# Connector_Sheet.net
KiCad netlist of a schematic drawn in Altium Designer
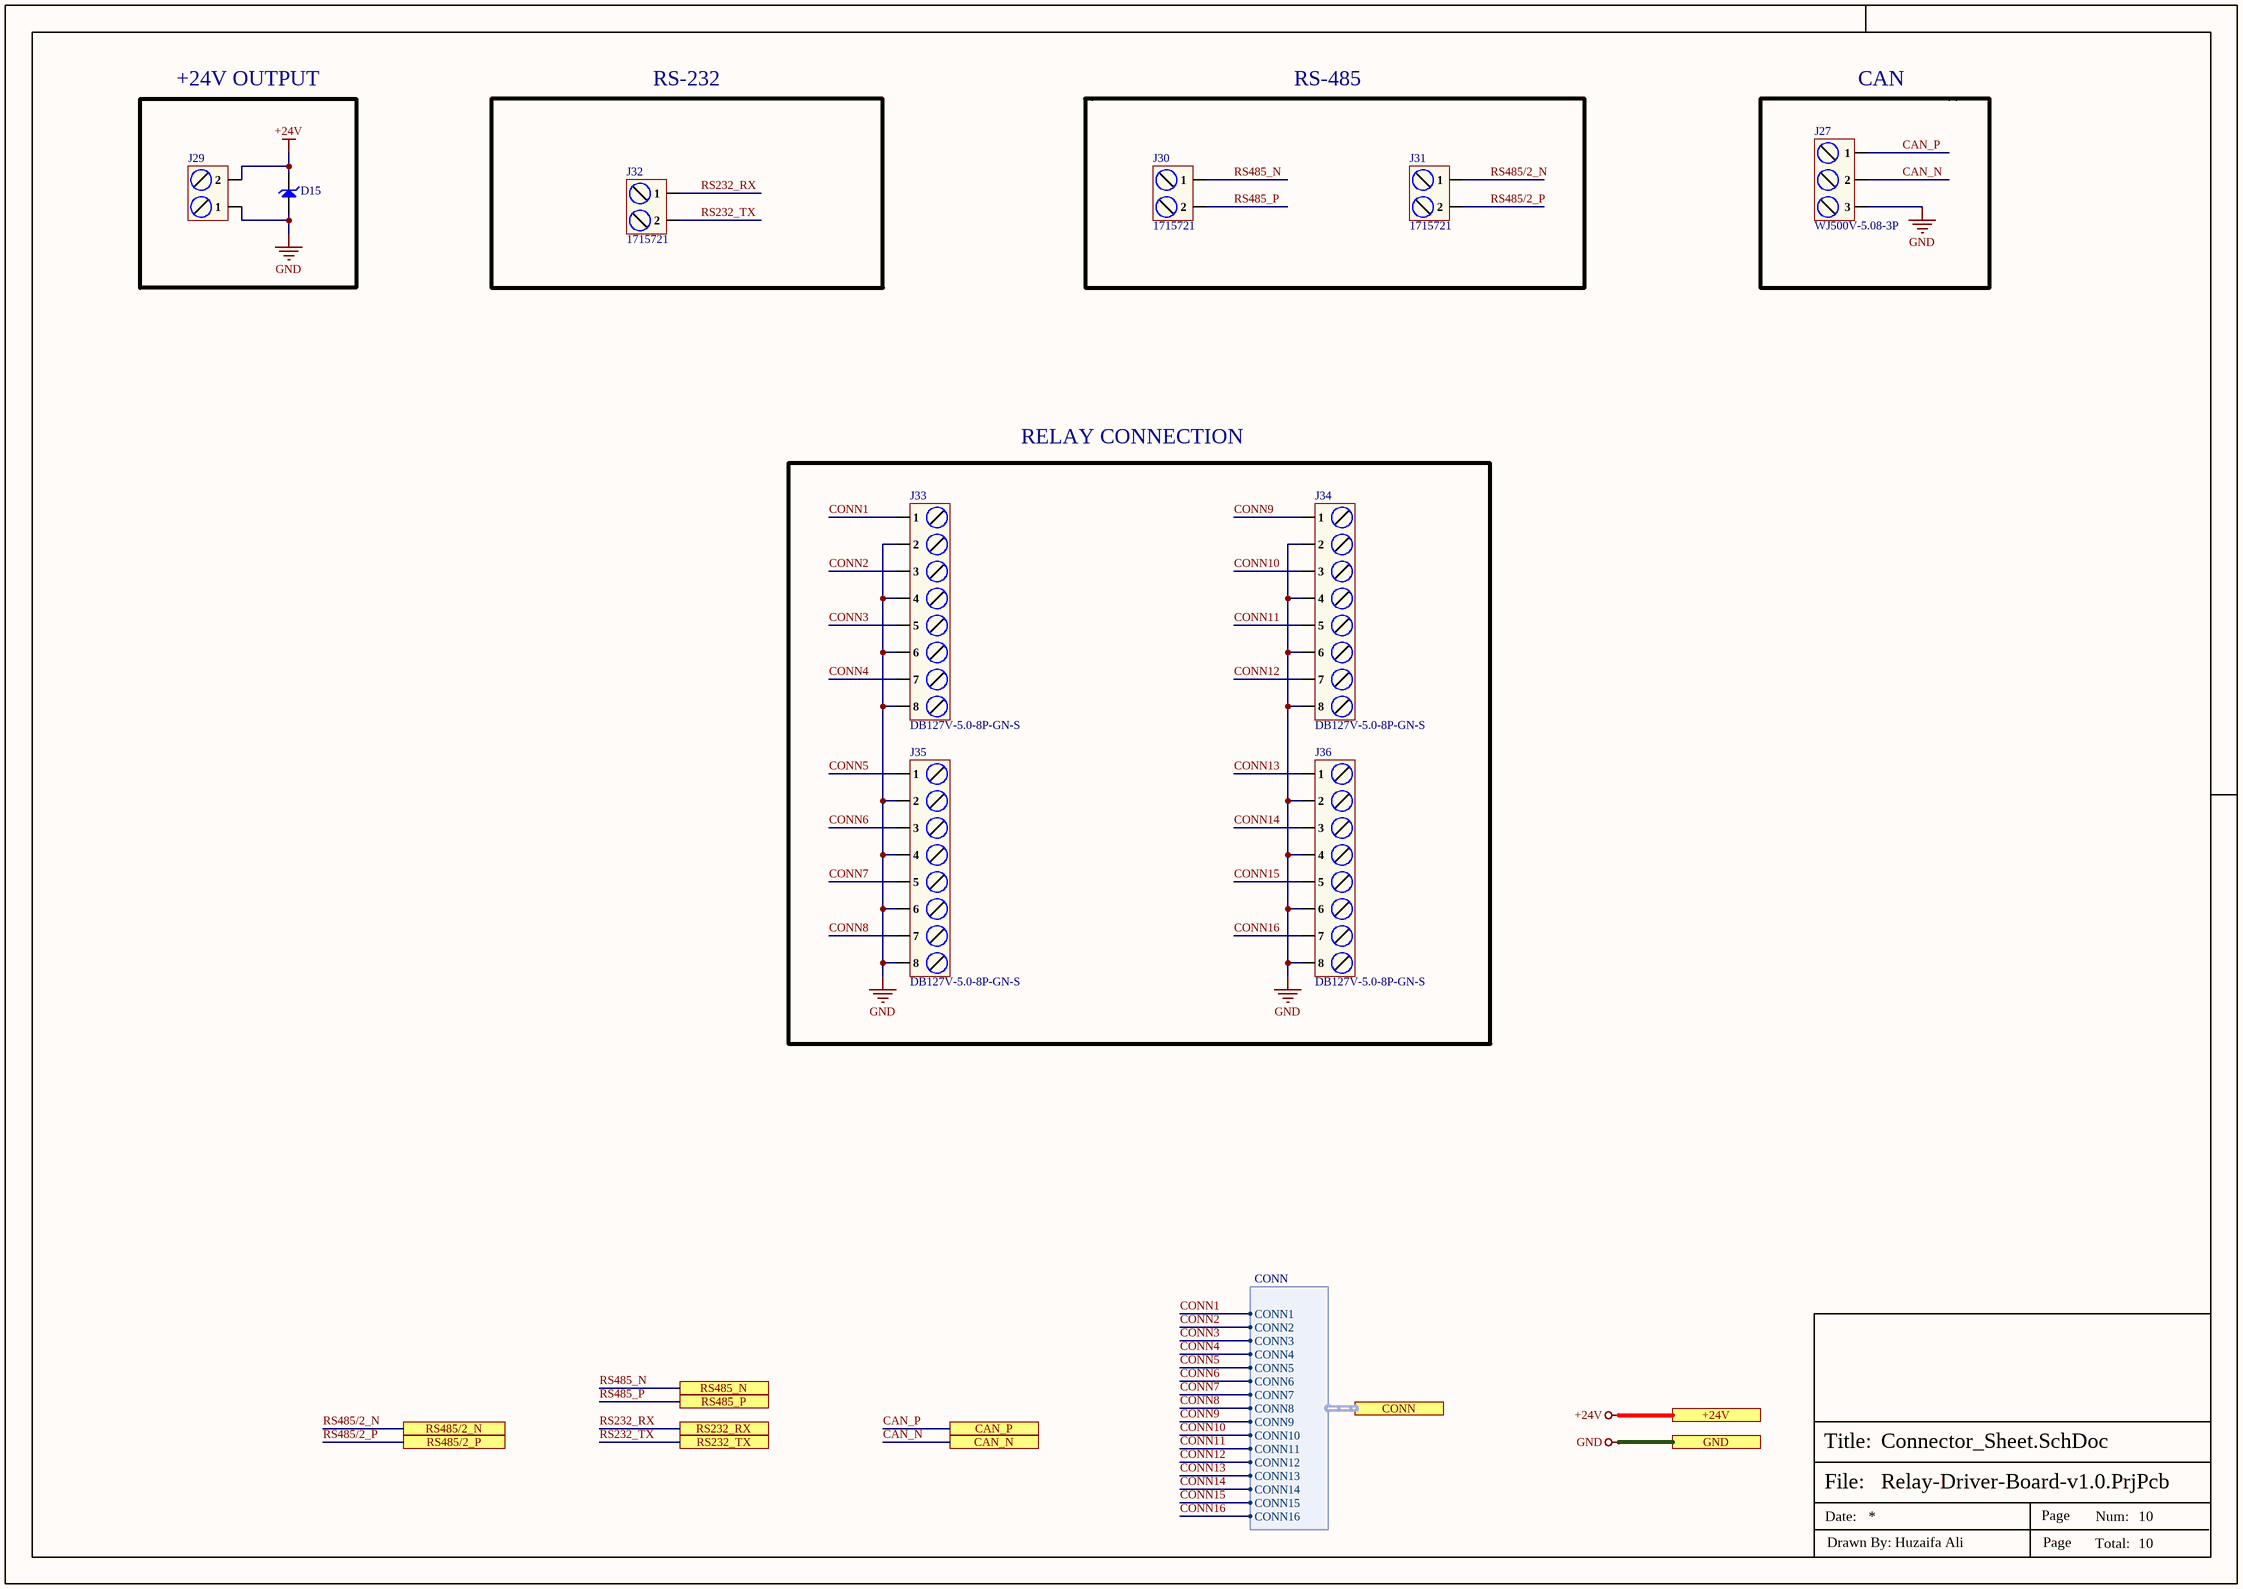
[diagram p0: Connector_Sheet.SchDoc]

(export (version "E")
  (design (tool "Eeschema 10.0.6"))
  (components
    (comp (ref "D15")
      (value "SMBJ28A-13-F")
      (footprint "SMB_")
      (description "TVS DIODE 28VWM 45.4VC SMB")
      (fields (field (name "MANUFACTURER") "Diodes"))
      (libsource (lib "eSpark Libraries") (part "SMBJ28A-13-F"))
    )
    (comp (ref "J27")
      (value "WJ500V-5.08-3P")
      (footprint "WJ500V-5.08-3P")
      (fields (field (name "MANUFACTURER") "Ningbo Kangnex Elec") (field (name "LCSC PART NUMBER") "C72334"))
      (libsource (lib "eSpark Libraries") (part "WJ500V-5.08-3P"))
    )
    (comp (ref "J29")
      (value "MXHB9500-9.5-02P-BK01-Cu-S-A")
      (footprint "MXHB9500-9.5-02P-BK01-Cu-S-A")
      (fields (field (name "MANUFACTURER") "MAX") (field (name "LCSC PART NUMBER") "C7542168"))
      (libsource (lib "eSpark Libraries") (part "MXHB9500-9.5-02P-BK01-Cu-S-A"))
    )
    (comp (ref "J30")
      (value "1715721")
      (footprint "1715721")
      (description "TERM BLK 2P SIDE ENT 5.08MM PCB")
      (fields (field (name "MANUFACTURER") "Phoenix Contact"))
      (libsource (lib "eSpark Libraries") (part "1715721"))
    )
    (comp (ref "J31")
      (value "1715721")
      (footprint "1715721")
      (description "TERM BLK 2P SIDE ENT 5.08MM PCB")
      (fields (field (name "MANUFACTURER") "Phoenix Contact"))
      (libsource (lib "eSpark Libraries") (part "1715721"))
    )
    (comp (ref "J32")
      (value "1715721")
      (footprint "1715721")
      (description "TERM BLK 2P SIDE ENT 5.08MM PCB")
      (fields (field (name "MANUFACTURER") "Phoenix Contact"))
      (libsource (lib "eSpark Libraries") (part "1715721"))
    )
    (comp (ref "J33")
      (value "DB127V-5.0-8P-GN-S")
      (footprint "DB127V-5.0-8P-GN-S")
      (description "1x8P -40℃~+105℃ 15A 250V Green 14~26 Straight 5mm 1.5 1 8 Plugin,P=5mm Screw Terminal Blocks ROHS")
      (fields (field (name "LCSC PART NUMBER") "C430626") (field (name "MANUFACTURER") "DIBO"))
      (libsource (lib "eSpark Libraries") (part "DB127V-5.0-8P-GN-S"))
    )
    (comp (ref "J34")
      (value "DB127V-5.0-8P-GN-S")
      (footprint "DB127V-5.0-8P-GN-S")
      (description "1x8P -40℃~+105℃ 15A 250V Green 14~26 Straight 5mm 1.5 1 8 Plugin,P=5mm Screw Terminal Blocks ROHS")
      (fields (field (name "LCSC PART NUMBER") "C430626") (field (name "MANUFACTURER") "DIBO"))
      (libsource (lib "eSpark Libraries") (part "DB127V-5.0-8P-GN-S"))
    )
    (comp (ref "J35")
      (value "DB127V-5.0-8P-GN-S")
      (footprint "DB127V-5.0-8P-GN-S")
      (description "1x8P -40℃~+105℃ 15A 250V Green 14~26 Straight 5mm 1.5 1 8 Plugin,P=5mm Screw Terminal Blocks ROHS")
      (fields (field (name "LCSC PART NUMBER") "C430626") (field (name "MANUFACTURER") "DIBO"))
      (libsource (lib "eSpark Libraries") (part "DB127V-5.0-8P-GN-S"))
    )
    (comp (ref "J36")
      (value "DB127V-5.0-8P-GN-S")
      (footprint "DB127V-5.0-8P-GN-S")
      (description "1x8P -40℃~+105℃ 15A 250V Green 14~26 Straight 5mm 1.5 1 8 Plugin,P=5mm Screw Terminal Blocks ROHS")
      (fields (field (name "LCSC PART NUMBER") "C430626") (field (name "MANUFACTURER") "DIBO"))
      (libsource (lib "eSpark Libraries") (part "DB127V-5.0-8P-GN-S"))
    )
  )
  (nets
    (net (code "2") (name "+24V") (class "Default")
      (node (ref "D15") (pin "2") (pinfunction "K_2") (pintype "passive"))
      (node (ref "J29") (pin "2") (pinfunction "2_2") (pintype "passive"))
    )
    (net (code "3") (name "/CAN_N") (class "Default")
      (node (ref "J27") (pin "2") (pinfunction "2_2") (pintype "passive"))
    )
    (net (code "4") (name "/CAN_P") (class "Default")
      (node (ref "J27") (pin "1") (pinfunction "1_1") (pintype "passive"))
    )
    (net (code "5") (name "/CONN1") (class "Default")
      (node (ref "J33") (pin "1") (pinfunction "1_1") (pintype "passive"))
    )
    (net (code "6") (name "/CONN2") (class "Default")
      (node (ref "J33") (pin "3") (pinfunction "3_3") (pintype "passive"))
    )
    (net (code "7") (name "/CONN3") (class "Default")
      (node (ref "J33") (pin "5") (pinfunction "5_5") (pintype "passive"))
    )
    (net (code "8") (name "/CONN4") (class "Default")
      (node (ref "J33") (pin "7") (pinfunction "7_7") (pintype "passive"))
    )
    (net (code "9") (name "/CONN5") (class "Default")
      (node (ref "J35") (pin "1") (pinfunction "1_1") (pintype "passive"))
    )
    (net (code "10") (name "/CONN6") (class "Default")
      (node (ref "J35") (pin "3") (pinfunction "3_3") (pintype "passive"))
    )
    (net (code "11") (name "/CONN7") (class "Default")
      (node (ref "J35") (pin "5") (pinfunction "5_5") (pintype "passive"))
    )
    (net (code "12") (name "/CONN8") (class "Default")
      (node (ref "J35") (pin "7") (pinfunction "7_7") (pintype "passive"))
    )
    (net (code "13") (name "/CONN9") (class "Default")
      (node (ref "J34") (pin "1") (pinfunction "1_1") (pintype "passive"))
    )
    (net (code "14") (name "/CONN10") (class "Default")
      (node (ref "J34") (pin "3") (pinfunction "3_3") (pintype "passive"))
    )
    (net (code "15") (name "/CONN11") (class "Default")
      (node (ref "J34") (pin "5") (pinfunction "5_5") (pintype "passive"))
    )
    (net (code "16") (name "/CONN12") (class "Default")
      (node (ref "J34") (pin "7") (pinfunction "7_7") (pintype "passive"))
    )
    (net (code "17") (name "/CONN13") (class "Default")
      (node (ref "J36") (pin "1") (pinfunction "1_1") (pintype "passive"))
    )
    (net (code "18") (name "/CONN14") (class "Default")
      (node (ref "J36") (pin "3") (pinfunction "3_3") (pintype "passive"))
    )
    (net (code "19") (name "/CONN15") (class "Default")
      (node (ref "J36") (pin "5") (pinfunction "5_5") (pintype "passive"))
    )
    (net (code "20") (name "/CONN16") (class "Default")
      (node (ref "J36") (pin "7") (pinfunction "7_7") (pintype "passive"))
    )
    (net (code "21") (name "/RS232_RX") (class "Default")
      (node (ref "J32") (pin "1") (pinfunction "1_1") (pintype "passive"))
    )
    (net (code "22") (name "/RS232_TX") (class "Default")
      (node (ref "J32") (pin "2") (pinfunction "2_2") (pintype "passive"))
    )
    (net (code "23") (name "/RS485_N") (class "Default")
      (node (ref "J30") (pin "1") (pinfunction "1_1") (pintype "passive"))
    )
    (net (code "24") (name "/RS485_P") (class "Default")
      (node (ref "J30") (pin "2") (pinfunction "2_2") (pintype "passive"))
    )
    (net (code "25") (name "/RS485{slash}2_N") (class "Default")
      (node (ref "J31") (pin "1") (pinfunction "1_1") (pintype "passive"))
    )
    (net (code "26") (name "/RS485{slash}2_P") (class "Default")
      (node (ref "J31") (pin "2") (pinfunction "2_2") (pintype "passive"))
    )
    (net (code "28") (name "GND") (class "Default")
      (node (ref "D15") (pin "1") (pinfunction "A_1") (pintype "passive"))
      (node (ref "J27") (pin "3") (pinfunction "3_3") (pintype "passive"))
      (node (ref "J29") (pin "1") (pinfunction "1_1") (pintype "passive"))
      (node (ref "J33") (pin "2") (pinfunction "2_2") (pintype "passive"))
      (node (ref "J33") (pin "4") (pinfunction "4_4") (pintype "passive"))
      (node (ref "J33") (pin "6") (pinfunction "6_6") (pintype "passive"))
      (node (ref "J33") (pin "8") (pinfunction "8_8") (pintype "passive"))
      (node (ref "J34") (pin "2") (pinfunction "2_2") (pintype "passive"))
      (node (ref "J34") (pin "4") (pinfunction "4_4") (pintype "passive"))
      (node (ref "J34") (pin "6") (pinfunction "6_6") (pintype "passive"))
      (node (ref "J34") (pin "8") (pinfunction "8_8") (pintype "passive"))
      (node (ref "J35") (pin "2") (pinfunction "2_2") (pintype "passive"))
      (node (ref "J35") (pin "4") (pinfunction "4_4") (pintype "passive"))
      (node (ref "J35") (pin "6") (pinfunction "6_6") (pintype "passive"))
      (node (ref "J35") (pin "8") (pinfunction "8_8") (pintype "passive"))
      (node (ref "J36") (pin "2") (pinfunction "2_2") (pintype "passive"))
      (node (ref "J36") (pin "4") (pinfunction "4_4") (pintype "passive"))
      (node (ref "J36") (pin "6") (pinfunction "6_6") (pintype "passive"))
      (node (ref "J36") (pin "8") (pinfunction "8_8") (pintype "passive"))
    )
  )
)
